# Gas_Gauge.net
KiCad netlist of a schematic drawn in Altium Designer
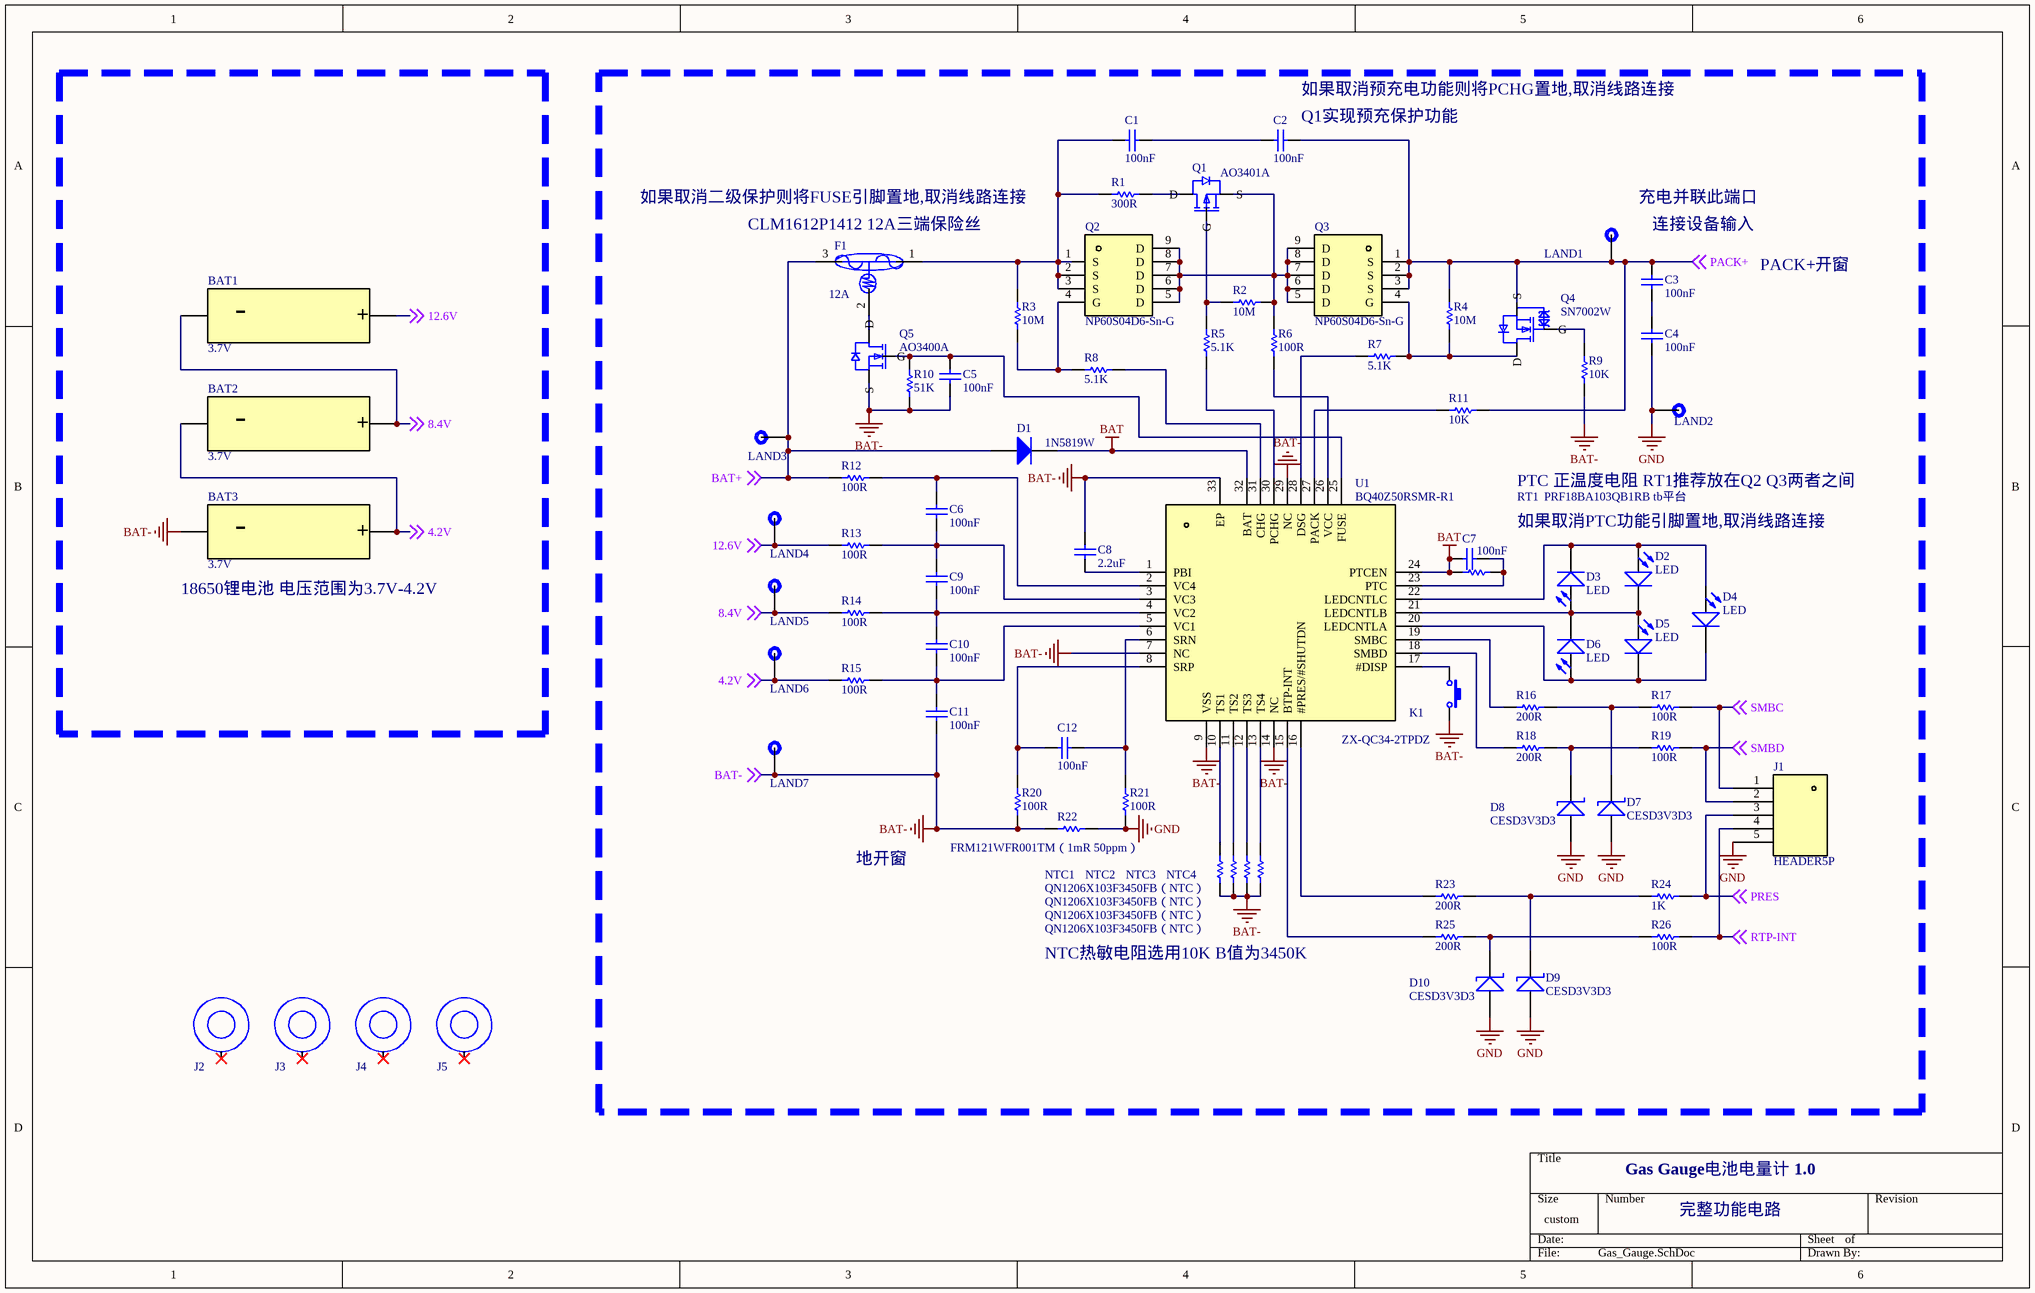
[diagram p0: Gas_Gauge.SchDoc]

(export (version "E")
  (design (tool "Eeschema 10.0.6"))
  (components
    (comp (ref "BAT1")
      (value "3.7V")
      (footprint "BH-18650-B1BA002")
      (description "适用电池18650平头电芯座")
      (libsource (lib "LinComponent") (part "BH-18650-B1BA002"))
    )
    (comp (ref "BAT2")
      (value "3.7V")
      (footprint "BH-18650-B1BA002")
      (description "适用电池18650平头电芯座")
      (libsource (lib "LinComponent") (part "BH-18650-B1BA002"))
    )
    (comp (ref "BAT3")
      (value "3.7V")
      (footprint "BH-18650-B1BA002")
      (description "适用电池18650平头电芯座")
      (libsource (lib "LinComponent") (part "BH-18650-B1BA002"))
    )
    (comp (ref "C1")
      (value "100nF")
      (footprint "C0603")
      (description "独石电容")
      (libsource (lib "LinComponent") (part "CAP"))
    )
    (comp (ref "C2")
      (value "100nF")
      (footprint "C0603")
      (description "独石电容")
      (libsource (lib "LinComponent") (part "CAP"))
    )
    (comp (ref "C3")
      (value "100nF")
      (footprint "C0805")
      (description "独石电容")
      (libsource (lib "LinComponent") (part "CAP"))
    )
    (comp (ref "C4")
      (value "100nF")
      (footprint "C0805")
      (description "独石电容")
      (libsource (lib "LinComponent") (part "CAP"))
    )
    (comp (ref "C5")
      (value "100nF")
      (footprint "C0603")
      (description "独石电容")
      (libsource (lib "LinComponent") (part "CAP"))
    )
    (comp (ref "C6")
      (value "100nF")
      (footprint "C0603")
      (description "独石电容")
      (libsource (lib "LinComponent") (part "CAP"))
    )
    (comp (ref "C7")
      (value "100nF")
      (footprint "C0603")
      (description "独石电容")
      (libsource (lib "LinComponent") (part "CAP"))
    )
    (comp (ref "C8")
      (value "2.2uF")
      (footprint "C0603")
      (description "独石电容")
      (libsource (lib "LinComponent") (part "CAP"))
    )
    (comp (ref "C9")
      (value "100nF")
      (footprint "C0603")
      (description "独石电容")
      (libsource (lib "LinComponent") (part "CAP"))
    )
    (comp (ref "C10")
      (value "100nF")
      (footprint "C0603")
      (description "独石电容")
      (libsource (lib "LinComponent") (part "CAP"))
    )
    (comp (ref "C11")
      (value "100nF")
      (footprint "C0603")
      (description "独石电容")
      (libsource (lib "LinComponent") (part "CAP"))
    )
    (comp (ref "C12")
      (value "100nF")
      (footprint "C0603")
      (description "独石电容")
      (libsource (lib "LinComponent") (part "CAP"))
    )
    (comp (ref "D1")
      (value "1N5819W")
      (footprint "DIODE_SOD-123")
      (description "二极管")
      (fields (field (name "PUBLISHER") "Altium Limited"))
      (libsource (lib "LinComponent") (part "DIODE"))
    )
    (comp (ref "D2")
      (value "LED")
      (footprint "LED0603")
      (description "贴片LED")
      (libsource (lib "LinComponent") (part "LED"))
    )
    (comp (ref "D3")
      (value "LED")
      (footprint "LED0603")
      (description "贴片LED")
      (libsource (lib "LinComponent") (part "LED"))
    )
    (comp (ref "D4")
      (value "LED")
      (footprint "LED0603")
      (description "贴片LED")
      (libsource (lib "LinComponent") (part "LED"))
    )
    (comp (ref "D5")
      (value "LED")
      (footprint "LED0603")
      (description "贴片LED")
      (libsource (lib "LinComponent") (part "LED"))
    )
    (comp (ref "D6")
      (value "LED")
      (footprint "LED0603")
      (description "贴片LED")
      (libsource (lib "LinComponent") (part "LED"))
    )
    (comp (ref "D7")
      (value "CESD3V3D3")
      (footprint "CESD3V3D3")
      (description "静电和浪涌保护(TVS),反向截止电压(Vrwm):3.3V,钳位电压:13V,峰值脉冲电流(Ipp):16A。")
      (libsource (lib "LinComponent") (part "CESD3V3D3"))
    )
    (comp (ref "D8")
      (value "CESD3V3D3")
      (footprint "CESD3V3D3")
      (description "静电和浪涌保护(TVS),反向截止电压(Vrwm):3.3V,钳位电压:13V,峰值脉冲电流(Ipp):16A。")
      (libsource (lib "LinComponent") (part "CESD3V3D3"))
    )
    (comp (ref "D9")
      (value "CESD3V3D3")
      (footprint "CESD3V3D3")
      (description "静电和浪涌保护(TVS),反向截止电压(Vrwm):3.3V,钳位电压:13V,峰值脉冲电流(Ipp):16A。")
      (libsource (lib "LinComponent") (part "CESD3V3D3"))
    )
    (comp (ref "D10")
      (value "CESD3V3D3")
      (footprint "CESD3V3D3")
      (description "静电和浪涌保护(TVS),反向截止电压(Vrwm):3.3V,钳位电压:13V,峰值脉冲电流(Ipp):16A。")
      (libsource (lib "LinComponent") (part "CESD3V3D3"))
    )
    (comp (ref "F1")
      (value "12A")
      (footprint "CLM1612P1412")
      (description "4串锂电池三端保险丝 12A")
      (libsource (lib "LinComponent") (part "CLM1612P1412"))
    )
    (comp (ref "J1")
      (value "HEADER5P")
      (footprint "HEADER5P")
      (description "5P排针")
      (libsource (lib "LinComponent") (part "HEADER5P"))
    )
    (comp (ref "J2")
      (value "NONE")
      (footprint "J-LOCATION")
      (description "定位孔")
      (libsource (lib "LinComponent") (part "J-LOCATION"))
    )
    (comp (ref "J3")
      (value "NONE")
      (footprint "J-LOCATION")
      (description "定位孔")
      (libsource (lib "LinComponent") (part "J-LOCATION"))
    )
    (comp (ref "J4")
      (value "NONE")
      (footprint "J-LOCATION")
      (description "定位孔")
      (libsource (lib "LinComponent") (part "J-LOCATION"))
    )
    (comp (ref "J5")
      (value "NONE")
      (footprint "J-LOCATION")
      (description "定位孔")
      (libsource (lib "LinComponent") (part "J-LOCATION"))
    )
    (comp (ref "K1")
      (value "ZX-QC34-2TPDZ")
      (footprint "ZX-QC34-2TPDZ")
      (description "3*4*2贴片开关带柱")
      (libsource (lib "LinComponent") (part "ZX-QC34-2TPDZ"))
    )
    (comp (ref "LAND1")
      (value "LAND")
      (footprint "LAND")
      (description "测试焊盘")
      (libsource (lib "LinComponent") (part "LAND"))
    )
    (comp (ref "LAND2")
      (value "LAND")
      (footprint "LAND")
      (description "测试焊盘")
      (libsource (lib "LinComponent") (part "LAND"))
    )
    (comp (ref "LAND3")
      (value "LAND")
      (footprint "LAND")
      (description "测试焊盘")
      (libsource (lib "LinComponent") (part "LAND"))
    )
    (comp (ref "LAND4")
      (value "LAND")
      (footprint "LAND1")
      (description "测试焊盘")
      (libsource (lib "LinComponent") (part "LAND"))
    )
    (comp (ref "LAND5")
      (value "LAND")
      (footprint "LAND1")
      (description "测试焊盘")
      (libsource (lib "LinComponent") (part "LAND"))
    )
    (comp (ref "LAND6")
      (value "LAND")
      (footprint "LAND1")
      (description "测试焊盘")
      (libsource (lib "LinComponent") (part "LAND"))
    )
    (comp (ref "LAND7")
      (value "LAND")
      (footprint "LAND")
      (description "测试焊盘")
      (libsource (lib "LinComponent") (part "LAND"))
    )
    (comp (ref "NTC1")
      (value "QN1206X103F3450FB（NTC）")
      (footprint "R1206")
      (description "电阻")
      (libsource (lib "LinComponent") (part "RES"))
    )
    (comp (ref "NTC2")
      (value "QN1206X103F3450FB（NTC）")
      (footprint "R1206")
      (description "电阻")
      (libsource (lib "LinComponent") (part "RES"))
    )
    (comp (ref "NTC3")
      (value "QN1206X103F3450FB（NTC）")
      (footprint "R1206")
      (description "电阻")
      (libsource (lib "LinComponent") (part "RES"))
    )
    (comp (ref "NTC4")
      (value "QN1206X103F3450FB（NTC）")
      (footprint "R1206")
      (description "电阻")
      (libsource (lib "LinComponent") (part "RES"))
    )
    (comp (ref "Q1")
      (value "AO3401A")
      (footprint "AO3401A")
      (description "PMOS UMW(友台半导体) \r\n漏源电压(Vdss):30V\r\n连续漏极电流(Id):4.2A\r\n导通电阻(RDS(on)):50mΩ@10V")
      (libsource (lib "LinComponent") (part "AO3401A"))
    )
    (comp (ref "Q2")
      (value "NP60S04D6-Sn-G")
      (footprint "NP60S04D6-Sn-G")
      (description "NMOS natlinear(南麟)\r\n漏源电压(Vdss):40V\r\n连续漏极电流(Id):60A\r\n导通电阻(RDS(on)):5.9mR")
      (libsource (lib "LinComponent") (part "NP60S04D6-Sn-G"))
    )
    (comp (ref "Q3")
      (value "NP60S04D6-Sn-G")
      (footprint "NP60S04D6-Sn-G")
      (description "NMOS natlinear(南麟)\r\n漏源电压(Vdss):40V\r\n连续漏极电流(Id):60A\r\n导通电阻(RDS(on)):5.9mR")
      (libsource (lib "") (part "NP60S04D6-Sn-G_1"))
    )
    (comp (ref "Q4")
      (value "SN7002W")
      (footprint "SN7002W")
      (description "NMOS Leiditech(雷卯电子) \r\n漏源电压(Vdss):60V\r\n连续漏极电流(Id):115mA\r\n导通电阻(RDS(on)):1.4Ω")
      (libsource (lib "LinComponent") (part "SN7002W"))
    )
    (comp (ref "Q5")
      (value "AO3400A")
      (footprint "AO3400A")
      (description "NMOS UMW(友台半导体) \r\n漏源电压(Vdss):30V\r\n连续漏极电流(Id):5.8A\r\n耗散功率(Pd):1.4W。")
      (libsource (lib "LinComponent") (part "AO3400A"))
    )
    (comp (ref "R1")
      (value "300R")
      (footprint "R1812")
      (description "电阻")
      (libsource (lib "LinComponent") (part "RES"))
    )
    (comp (ref "R2")
      (value "10M")
      (footprint "R0603")
      (description "电阻")
      (libsource (lib "LinComponent") (part "RES"))
    )
    (comp (ref "R3")
      (value "10M")
      (footprint "R0603")
      (description "电阻")
      (libsource (lib "LinComponent") (part "RES"))
    )
    (comp (ref "R4")
      (value "10M")
      (footprint "R0603")
      (description "电阻")
      (libsource (lib "LinComponent") (part "RES"))
    )
    (comp (ref "R5")
      (value "5.1K")
      (footprint "R0603")
      (description "电阻")
      (libsource (lib "LinComponent") (part "RES"))
    )
    (comp (ref "R6")
      (value "100R")
      (footprint "R0603")
      (description "电阻")
      (libsource (lib "LinComponent") (part "RES"))
    )
    (comp (ref "R7")
      (value "5.1K")
      (footprint "R0603")
      (description "电阻")
      (libsource (lib "LinComponent") (part "RES"))
    )
    (comp (ref "R8")
      (value "5.1K")
      (footprint "R0603")
      (description "电阻")
      (libsource (lib "LinComponent") (part "RES"))
    )
    (comp (ref "R9")
      (value "10K")
      (footprint "R0603")
      (description "电阻")
      (libsource (lib "LinComponent") (part "RES"))
    )
    (comp (ref "R10")
      (value "51K")
      (footprint "R0603")
      (description "电阻")
      (libsource (lib "LinComponent") (part "RES"))
    )
    (comp (ref "R11")
      (value "10K")
      (footprint "R0603")
      (description "电阻")
      (libsource (lib "LinComponent") (part "RES"))
    )
    (comp (ref "R12")
      (value "100R")
      (footprint "R0603")
      (description "电阻")
      (libsource (lib "LinComponent") (part "RES"))
    )
    (comp (ref "R13")
      (value "100R")
      (footprint "R0603")
      (description "电阻")
      (libsource (lib "LinComponent") (part "RES"))
    )
    (comp (ref "R14")
      (value "100R")
      (footprint "R0603")
      (description "电阻")
      (libsource (lib "LinComponent") (part "RES"))
    )
    (comp (ref "R15")
      (value "100R")
      (footprint "R0603")
      (description "电阻")
      (libsource (lib "LinComponent") (part "RES"))
    )
    (comp (ref "R16")
      (value "200R")
      (footprint "R0603")
      (description "电阻")
      (libsource (lib "LinComponent") (part "RES"))
    )
    (comp (ref "R17")
      (value "100R")
      (footprint "R0603")
      (description "电阻")
      (libsource (lib "LinComponent") (part "RES"))
    )
    (comp (ref "R18")
      (value "200R")
      (footprint "R0603")
      (description "电阻")
      (libsource (lib "LinComponent") (part "RES"))
    )
    (comp (ref "R19")
      (value "100R")
      (footprint "R0603")
      (description "电阻")
      (libsource (lib "LinComponent") (part "RES"))
    )
    (comp (ref "R20")
      (value "100R")
      (footprint "R0603")
      (description "电阻")
      (libsource (lib "LinComponent") (part "RES"))
    )
    (comp (ref "R21")
      (value "100R")
      (footprint "R0603")
      (description "电阻")
      (libsource (lib "LinComponent") (part "RES"))
    )
    (comp (ref "R22")
      (value "FRM121WFR001TM（1mR 50ppm）")
      (footprint "R1206")
      (description "电阻")
      (libsource (lib "LinComponent") (part "RES"))
    )
    (comp (ref "R23")
      (value "200R")
      (footprint "R0603")
      (description "电阻")
      (libsource (lib "LinComponent") (part "RES"))
    )
    (comp (ref "R24")
      (value "1K")
      (footprint "R0603")
      (description "电阻")
      (libsource (lib "LinComponent") (part "RES"))
    )
    (comp (ref "R25")
      (value "200R")
      (footprint "R0603")
      (description "电阻")
      (libsource (lib "LinComponent") (part "RES"))
    )
    (comp (ref "R26")
      (value "100R")
      (footprint "R0603")
      (description "电阻")
      (libsource (lib "LinComponent") (part "RES"))
    )
    (comp (ref "RT1")
      (value "PRF18BA103QB1RB tb平台")
      (footprint "R0603")
      (description "电阻")
      (libsource (lib "LinComponent") (part "RES"))
    )
    (comp (ref "U1")
      (value "BQ40Z50RSMR-R1")
      (footprint "BQ40Z50RSMR-R1")
      (description "BQ40Z50-R1支持涡轮模式1.0的1至4节串联锂离子电池组管理器(锂电池电量计)")
      (libsource (lib "LinComponent") (part "BQ40Z50RSMR-R1"))
    )
  )
  (nets
    (net (code "1") (name "4.2V") (class "Default")
      (node (ref "BAT2") (pin "1") (pinfunction "-_1") (pintype "passive"))
      (node (ref "BAT3") (pin "2") (pinfunction "+_2") (pintype "passive"))
      (node (ref "LAND6") (pin "1") (pinfunction "1_1") (pintype "passive"))
      (node (ref "R15") (pin "1") (pinfunction "1_1") (pintype "passive"))
    )
    (net (code "2") (name "8.4V") (class "Default")
      (node (ref "BAT1") (pin "1") (pinfunction "-_1") (pintype "passive"))
      (node (ref "BAT2") (pin "2") (pinfunction "+_2") (pintype "passive"))
      (node (ref "LAND5") (pin "1") (pinfunction "1_1") (pintype "passive"))
      (node (ref "R14") (pin "1") (pinfunction "1_1") (pintype "passive"))
    )
    (net (code "3") (name "12.6V") (class "Default")
      (node (ref "BAT1") (pin "2") (pinfunction "+_2") (pintype "passive"))
      (node (ref "LAND4") (pin "1") (pinfunction "1_1") (pintype "passive"))
      (node (ref "R13") (pin "1") (pinfunction "1_1") (pintype "passive"))
    )
    (net (code "4") (name "BAT") (class "Default")
      (node (ref "C7") (pin "1") (pinfunction "1_1") (pintype "passive"))
      (node (ref "D1") (pin "2") (pinfunction "K_2") (pintype "passive"))
      (node (ref "RT1") (pin "2") (pinfunction "2_2") (pintype "passive"))
      (node (ref "U1") (pin "24") (pinfunction "PTCEN_24") (pintype "passive"))
      (node (ref "U1") (pin "32") (pinfunction "BAT_32") (pintype "passive"))
    )
    (net (code "5") (name "BAT+") (class "Default")
      (node (ref "D1") (pin "1") (pinfunction "A_1") (pintype "passive"))
      (node (ref "F1") (pin "3") (pinfunction "3_3") (pintype "passive"))
      (node (ref "LAND3") (pin "1") (pinfunction "1_1") (pintype "passive"))
      (node (ref "R12") (pin "1") (pinfunction "1_1") (pintype "passive"))
    )
    (net (code "6") (name "BAT-") (class "Default")
      (node (ref "BAT3") (pin "1") (pinfunction "-_1") (pintype "passive"))
      (node (ref "C11") (pin "2") (pinfunction "2_2") (pintype "passive"))
      (node (ref "C5") (pin "2") (pinfunction "2_2") (pintype "passive"))
      (node (ref "C8") (pin "1") (pinfunction "1_1") (pintype "passive"))
      (node (ref "K1") (pin "2") (pinfunction "2_2") (pintype "passive"))
      (node (ref "LAND7") (pin "1") (pinfunction "1_1") (pintype "passive"))
      (node (ref "NTC1") (pin "1") (pinfunction "1_1") (pintype "passive"))
      (node (ref "NTC2") (pin "1") (pinfunction "1_1") (pintype "passive"))
      (node (ref "NTC3") (pin "1") (pinfunction "1_1") (pintype "passive"))
      (node (ref "NTC4") (pin "1") (pinfunction "1_1") (pintype "passive"))
      (node (ref "Q5") (pin "2") (pinfunction "S_2") (pintype "passive"))
      (node (ref "R10") (pin "1") (pinfunction "1_1") (pintype "passive"))
      (node (ref "R20") (pin "1") (pinfunction "1_1") (pintype "passive"))
      (node (ref "R22") (pin "1") (pinfunction "1_1") (pintype "passive"))
      (node (ref "R9") (pin "1") (pinfunction "1_1") (pintype "passive"))
      (node (ref "U1") (pin "14") (pinfunction "NC_14") (pintype "passive"))
      (node (ref "U1") (pin "29") (pinfunction "NC_29") (pintype "passive"))
      (node (ref "U1") (pin "33") (pinfunction "EP_33") (pintype "passive"))
      (node (ref "U1") (pin "7") (pinfunction "NC_7") (pintype "passive"))
      (node (ref "U1") (pin "9") (pinfunction "VSS_9") (pintype "passive"))
    )
    (net (code "7") (name "GND") (class "Default")
      (node (ref "C4") (pin "1") (pinfunction "1_1") (pintype "passive"))
      (node (ref "D10") (pin "2") (pinfunction "2_2") (pintype "passive"))
      (node (ref "D7") (pin "2") (pinfunction "2_2") (pintype "passive"))
      (node (ref "D8") (pin "2") (pinfunction "2_2") (pintype "passive"))
      (node (ref "D9") (pin "2") (pinfunction "2_2") (pintype "passive"))
      (node (ref "J1") (pin "5") (pinfunction "5_5") (pintype "passive"))
      (node (ref "LAND2") (pin "1") (pinfunction "1_1") (pintype "passive"))
      (node (ref "R21") (pin "1") (pinfunction "1_1") (pintype "passive"))
      (node (ref "R22") (pin "2") (pinfunction "2_2") (pintype "passive"))
    )
    (net (code "8") (name "Net-(C1-Pad1)") (class "Default")
      (node (ref "C1") (pin "1") (pinfunction "1_1") (pintype "passive"))
      (node (ref "C2") (pin "2") (pinfunction "2_2") (pintype "passive"))
    )
    (net (code "9") (name "Net-(C1-Pad2)") (class "Default")
      (node (ref "C1") (pin "2") (pinfunction "2_2") (pintype "passive"))
      (node (ref "F1") (pin "1") (pinfunction "1_1") (pintype "passive"))
      (node (ref "Q2") (pin "1") (pinfunction "S_1") (pintype "passive"))
      (node (ref "Q2") (pin "2") (pinfunction "S_2") (pintype "passive"))
      (node (ref "Q2") (pin "3") (pinfunction "S_3") (pintype "passive"))
      (node (ref "R1") (pin "1") (pinfunction "1_1") (pintype "passive"))
      (node (ref "R3") (pin "2") (pinfunction "2_2") (pintype "passive"))
    )
    (net (code "10") (name "Net-(C3-Pad2)") (class "Default")
      (node (ref "C3") (pin "2") (pinfunction "2_2") (pintype "passive"))
      (node (ref "C4") (pin "2") (pinfunction "2_2") (pintype "passive"))
    )
    (net (code "11") (name "Net-(D7-Pad1)") (class "Default")
      (node (ref "D7") (pin "1") (pinfunction "1_1") (pintype "passive"))
      (node (ref "R16") (pin "1") (pinfunction "1_1") (pintype "passive"))
      (node (ref "R17") (pin "2") (pinfunction "2_2") (pintype "passive"))
    )
    (net (code "12") (name "Net-(D8-Pad1)") (class "Default")
      (node (ref "D8") (pin "1") (pinfunction "1_1") (pintype "passive"))
      (node (ref "R18") (pin "1") (pinfunction "1_1") (pintype "passive"))
      (node (ref "R19") (pin "2") (pinfunction "2_2") (pintype "passive"))
    )
    (net (code "13") (name "Net-(D9-Pad1)") (class "Default")
      (node (ref "D9") (pin "1") (pinfunction "1_1") (pintype "passive"))
      (node (ref "R23") (pin "1") (pinfunction "1_1") (pintype "passive"))
      (node (ref "R24") (pin "2") (pinfunction "2_2") (pintype "passive"))
    )
    (net (code "14") (name "Net-(D10-Pad1)") (class "Default")
      (node (ref "D10") (pin "1") (pinfunction "1_1") (pintype "passive"))
      (node (ref "R25") (pin "1") (pinfunction "1_1") (pintype "passive"))
      (node (ref "R26") (pin "2") (pinfunction "2_2") (pintype "passive"))
    )
    (net (code "15") (name "Net-(Q1-D)") (class "Default")
      (node (ref "Q1") (pin "3") (pinfunction "D_3") (pintype "passive"))
      (node (ref "R1") (pin "2") (pinfunction "2_2") (pintype "passive"))
    )
    (net (code "16") (name "Net-(Q1-G)") (class "Default")
      (node (ref "Q1") (pin "1") (pinfunction "G_1") (pintype "passive"))
      (node (ref "R2") (pin "1") (pinfunction "1_1") (pintype "passive"))
      (node (ref "R5") (pin "2") (pinfunction "2_2") (pintype "passive"))
    )
    (net (code "17") (name "Net-(Q1-S)") (class "Default")
      (node (ref "Q1") (pin "2") (pinfunction "S_2") (pintype "passive"))
      (node (ref "Q2") (pin "5") (pinfunction "D_5") (pintype "passive"))
      (node (ref "Q2") (pin "6") (pinfunction "D_6") (pintype "passive"))
      (node (ref "Q2") (pin "7") (pinfunction "D_7") (pintype "passive"))
      (node (ref "Q2") (pin "8") (pinfunction "D_8") (pintype "passive"))
      (node (ref "Q2") (pin "9") (pinfunction "D_9") (pintype "passive"))
      (node (ref "Q3") (pin "5") (pinfunction "D_5") (pintype "passive"))
      (node (ref "Q3") (pin "6") (pinfunction "D_6") (pintype "passive"))
      (node (ref "Q3") (pin "7") (pinfunction "D_7") (pintype "passive"))
      (node (ref "Q3") (pin "8") (pinfunction "D_8") (pintype "passive"))
      (node (ref "Q3") (pin "9") (pinfunction "D_9") (pintype "passive"))
      (node (ref "R2") (pin "2") (pinfunction "2_2") (pintype "passive"))
      (node (ref "R6") (pin "2") (pinfunction "2_2") (pintype "passive"))
    )
    (net (code "18") (name "Net-(Q2-G)") (class "Default")
      (node (ref "Q2") (pin "4") (pinfunction "G_4") (pintype "passive"))
      (node (ref "R3") (pin "1") (pinfunction "1_1") (pintype "passive"))
      (node (ref "R8") (pin "2") (pinfunction "2_2") (pintype "passive"))
    )
    (net (code "19") (name "Net-(Q3-G)") (class "Default")
      (node (ref "Q3") (pin "4") (pinfunction "G_4") (pintype "passive"))
      (node (ref "Q4") (pin "3") (pinfunction "D_3") (pintype "passive"))
      (node (ref "R4") (pin "1") (pinfunction "1_1") (pintype "passive"))
      (node (ref "R7") (pin "2") (pinfunction "2_2") (pintype "passive"))
    )
    (net (code "20") (name "Net-(Q4-G)") (class "Default")
      (node (ref "Q4") (pin "1") (pinfunction "G_1") (pintype "passive"))
      (node (ref "R9") (pin "2") (pinfunction "2_2") (pintype "passive"))
    )
    (net (code "21") (name "Net-(Q5-D)") (class "Default")
      (node (ref "F1") (pin "2") (pinfunction "2_2") (pintype "passive"))
      (node (ref "Q5") (pin "3") (pinfunction "D_3") (pintype "passive"))
    )
    (net (code "22") (name "Net-(Q5-G)") (class "Default")
      (node (ref "C5") (pin "1") (pinfunction "1_1") (pintype "passive"))
      (node (ref "Q5") (pin "1") (pinfunction "G_1") (pintype "passive"))
      (node (ref "R10") (pin "2") (pinfunction "2_2") (pintype "passive"))
      (node (ref "U1") (pin "25") (pinfunction "FUSE_25") (pintype "passive"))
    )
    (net (code "23") (name "Net-(U1-#DISP)") (class "Default")
      (node (ref "K1") (pin "1") (pinfunction "1_1") (pintype "passive"))
      (node (ref "U1") (pin "17") (pinfunction "#DISP_17") (pintype "passive"))
    )
    (net (code "24") (name "Net-(U1-#PRES{slash}#SHUTDN)") (class "Default")
      (node (ref "R23") (pin "2") (pinfunction "2_2") (pintype "passive"))
      (node (ref "U1") (pin "16") (pinfunction "#PRES/#SHUTDN_16") (pintype "passive"))
    )
    (net (code "25") (name "Net-(U1-BTP-INT)") (class "Default")
      (node (ref "R25") (pin "2") (pinfunction "2_2") (pintype "passive"))
      (node (ref "U1") (pin "15") (pinfunction "BTP-INT_15") (pintype "passive"))
    )
    (net (code "26") (name "Net-(U1-CHG)") (class "Default")
      (node (ref "R8") (pin "1") (pinfunction "1_1") (pintype "passive"))
      (node (ref "U1") (pin "31") (pinfunction "CHG_31") (pintype "passive"))
    )
    (net (code "27") (name "Net-(U1-DSG)") (class "Default")
      (node (ref "R7") (pin "1") (pinfunction "1_1") (pintype "passive"))
      (node (ref "U1") (pin "28") (pinfunction "DSG_28") (pintype "passive"))
    )
    (net (code "28") (name "Net-(U1-LEDCNTLA)") (class "Default")
      (node (ref "D4") (pin "K") (pinfunction "K_K") (pintype "passive"))
      (node (ref "D5") (pin "K") (pinfunction "K_K") (pintype "passive"))
      (node (ref "D6") (pin "A") (pinfunction "A_A") (pintype "passive"))
      (node (ref "U1") (pin "20") (pinfunction "LEDCNTLA_20") (pintype "passive"))
    )
    (net (code "29") (name "Net-(U1-LEDCNTLB)") (class "Default")
      (node (ref "D2") (pin "K") (pinfunction "K_K") (pintype "passive"))
      (node (ref "D3") (pin "A") (pinfunction "A_A") (pintype "passive"))
      (node (ref "D5") (pin "A") (pinfunction "A_A") (pintype "passive"))
      (node (ref "D6") (pin "K") (pinfunction "K_K") (pintype "passive"))
      (node (ref "U1") (pin "21") (pinfunction "LEDCNTLB_21") (pintype "passive"))
    )
    (net (code "30") (name "Net-(U1-LEDCNTLC)") (class "Default")
      (node (ref "D2") (pin "A") (pinfunction "A_A") (pintype "passive"))
      (node (ref "D3") (pin "K") (pinfunction "K_K") (pintype "passive"))
      (node (ref "D4") (pin "A") (pinfunction "A_A") (pintype "passive"))
      (node (ref "U1") (pin "22") (pinfunction "LEDCNTLC_22") (pintype "passive"))
    )
    (net (code "31") (name "Net-(U1-PACK)") (class "Default")
      (node (ref "R11") (pin "2") (pinfunction "2_2") (pintype "passive"))
      (node (ref "U1") (pin "27") (pinfunction "PACK_27") (pintype "passive"))
    )
    (net (code "32") (name "Net-(U1-PBI)") (class "Default")
      (node (ref "C8") (pin "2") (pinfunction "2_2") (pintype "passive"))
      (node (ref "U1") (pin "1") (pinfunction "PBI_1") (pintype "passive"))
    )
    (net (code "33") (name "Net-(U1-PCHG)") (class "Default")
      (node (ref "R5") (pin "1") (pinfunction "1_1") (pintype "passive"))
      (node (ref "U1") (pin "30") (pinfunction "PCHG_30") (pintype "passive"))
    )
    (net (code "34") (name "Net-(U1-PTC)") (class "Default")
      (node (ref "C7") (pin "2") (pinfunction "2_2") (pintype "passive"))
      (node (ref "RT1") (pin "1") (pinfunction "1_1") (pintype "passive"))
      (node (ref "U1") (pin "23") (pinfunction "PTC_23") (pintype "passive"))
    )
    (net (code "35") (name "Net-(U1-SMBC)") (class "Default")
      (node (ref "R16") (pin "2") (pinfunction "2_2") (pintype "passive"))
      (node (ref "U1") (pin "19") (pinfunction "SMBC_19") (pintype "passive"))
    )
    (net (code "36") (name "Net-(U1-SMBD)") (class "Default")
      (node (ref "R18") (pin "2") (pinfunction "2_2") (pintype "passive"))
      (node (ref "U1") (pin "18") (pinfunction "SMBD_18") (pintype "passive"))
    )
    (net (code "37") (name "Net-(U1-SRN)") (class "Default")
      (node (ref "C12") (pin "2") (pinfunction "2_2") (pintype "passive"))
      (node (ref "R21") (pin "2") (pinfunction "2_2") (pintype "passive"))
      (node (ref "U1") (pin "6") (pinfunction "SRN_6") (pintype "passive"))
    )
    (net (code "38") (name "Net-(U1-SRP)") (class "Default")
      (node (ref "C12") (pin "1") (pinfunction "1_1") (pintype "passive"))
      (node (ref "R20") (pin "2") (pinfunction "2_2") (pintype "passive"))
      (node (ref "U1") (pin "8") (pinfunction "SRP_8") (pintype "passive"))
    )
    (net (code "39") (name "Net-(U1-TS1)") (class "Default")
      (node (ref "NTC1") (pin "2") (pinfunction "2_2") (pintype "passive"))
      (node (ref "U1") (pin "10") (pinfunction "TS1_10") (pintype "passive"))
    )
    (net (code "40") (name "Net-(U1-TS2)") (class "Default")
      (node (ref "NTC2") (pin "2") (pinfunction "2_2") (pintype "passive"))
      (node (ref "U1") (pin "11") (pinfunction "TS2_11") (pintype "passive"))
    )
    (net (code "41") (name "Net-(U1-TS3)") (class "Default")
      (node (ref "NTC3") (pin "2") (pinfunction "2_2") (pintype "passive"))
      (node (ref "U1") (pin "12") (pinfunction "TS3_12") (pintype "passive"))
    )
    (net (code "42") (name "Net-(U1-TS4)") (class "Default")
      (node (ref "NTC4") (pin "2") (pinfunction "2_2") (pintype "passive"))
      (node (ref "U1") (pin "13") (pinfunction "TS4_13") (pintype "passive"))
    )
    (net (code "43") (name "Net-(U1-VC1)") (class "Default")
      (node (ref "C10") (pin "2") (pinfunction "2_2") (pintype "passive"))
      (node (ref "C11") (pin "1") (pinfunction "1_1") (pintype "passive"))
      (node (ref "R15") (pin "2") (pinfunction "2_2") (pintype "passive"))
      (node (ref "U1") (pin "5") (pinfunction "VC1_5") (pintype "passive"))
    )
    (net (code "44") (name "Net-(U1-VC2)") (class "Default")
      (node (ref "C10") (pin "1") (pinfunction "1_1") (pintype "passive"))
      (node (ref "C9") (pin "2") (pinfunction "2_2") (pintype "passive"))
      (node (ref "R14") (pin "2") (pinfunction "2_2") (pintype "passive"))
      (node (ref "U1") (pin "4") (pinfunction "VC2_4") (pintype "passive"))
    )
    (net (code "45") (name "Net-(U1-VC3)") (class "Default")
      (node (ref "C6") (pin "2") (pinfunction "2_2") (pintype "passive"))
      (node (ref "C9") (pin "1") (pinfunction "1_1") (pintype "passive"))
      (node (ref "R13") (pin "2") (pinfunction "2_2") (pintype "passive"))
      (node (ref "U1") (pin "3") (pinfunction "VC3_3") (pintype "passive"))
    )
    (net (code "46") (name "Net-(U1-VC4)") (class "Default")
      (node (ref "C6") (pin "1") (pinfunction "1_1") (pintype "passive"))
      (node (ref "R12") (pin "2") (pinfunction "2_2") (pintype "passive"))
      (node (ref "U1") (pin "2") (pinfunction "VC4_2") (pintype "passive"))
    )
    (net (code "47") (name "Net-(U1-VCC)") (class "Default")
      (node (ref "R6") (pin "1") (pinfunction "1_1") (pintype "passive"))
      (node (ref "U1") (pin "26") (pinfunction "VCC_26") (pintype "passive"))
    )
    (net (code "48") (name "PACK+") (class "Default")
      (node (ref "C2") (pin "1") (pinfunction "1_1") (pintype "passive"))
      (node (ref "C3") (pin "1") (pinfunction "1_1") (pintype "passive"))
      (node (ref "LAND1") (pin "1") (pinfunction "1_1") (pintype "passive"))
      (node (ref "Q3") (pin "1") (pinfunction "S_1") (pintype "passive"))
      (node (ref "Q3") (pin "2") (pinfunction "S_2") (pintype "passive"))
      (node (ref "Q3") (pin "3") (pinfunction "S_3") (pintype "passive"))
      (node (ref "Q4") (pin "2") (pinfunction "S_2") (pintype "passive"))
      (node (ref "R11") (pin "1") (pinfunction "1_1") (pintype "passive"))
      (node (ref "R4") (pin "2") (pinfunction "2_2") (pintype "passive"))
    )
    (net (code "49") (name "PRES") (class "Default")
      (node (ref "J1") (pin "3") (pinfunction "3_3") (pintype "passive"))
      (node (ref "R24") (pin "1") (pinfunction "1_1") (pintype "passive"))
    )
    (net (code "50") (name "RTP-INT") (class "Default")
      (node (ref "J1") (pin "4") (pinfunction "4_4") (pintype "passive"))
      (node (ref "R26") (pin "1") (pinfunction "1_1") (pintype "passive"))
    )
    (net (code "51") (name "SMBC") (class "Default")
      (node (ref "J1") (pin "1") (pinfunction "1_1") (pintype "passive"))
      (node (ref "R17") (pin "1") (pinfunction "1_1") (pintype "passive"))
    )
    (net (code "52") (name "SMBD") (class "Default")
      (node (ref "J1") (pin "2") (pinfunction "2_2") (pintype "passive"))
      (node (ref "R19") (pin "1") (pinfunction "1_1") (pintype "passive"))
    )
    (net (code "53") (name "unconnected-(J2-Loc-Pad0)") (class "Default")
      (node (ref "J2") (pin "0") (pinfunction "Loc_0") (pintype "passive+no_connect"))
    )
    (net (code "54") (name "unconnected-(J3-Loc-Pad0)") (class "Default")
      (node (ref "J3") (pin "0") (pinfunction "Loc_0") (pintype "passive+no_connect"))
    )
    (net (code "55") (name "unconnected-(J4-Loc-Pad0)") (class "Default")
      (node (ref "J4") (pin "0") (pinfunction "Loc_0") (pintype "passive+no_connect"))
    )
    (net (code "56") (name "unconnected-(J5-Loc-Pad0)") (class "Default")
      (node (ref "J5") (pin "0") (pinfunction "Loc_0") (pintype "passive+no_connect"))
    )
  )
)
